# relaymodule.net
KiCad netlist of a schematic drawn in Altium Designer
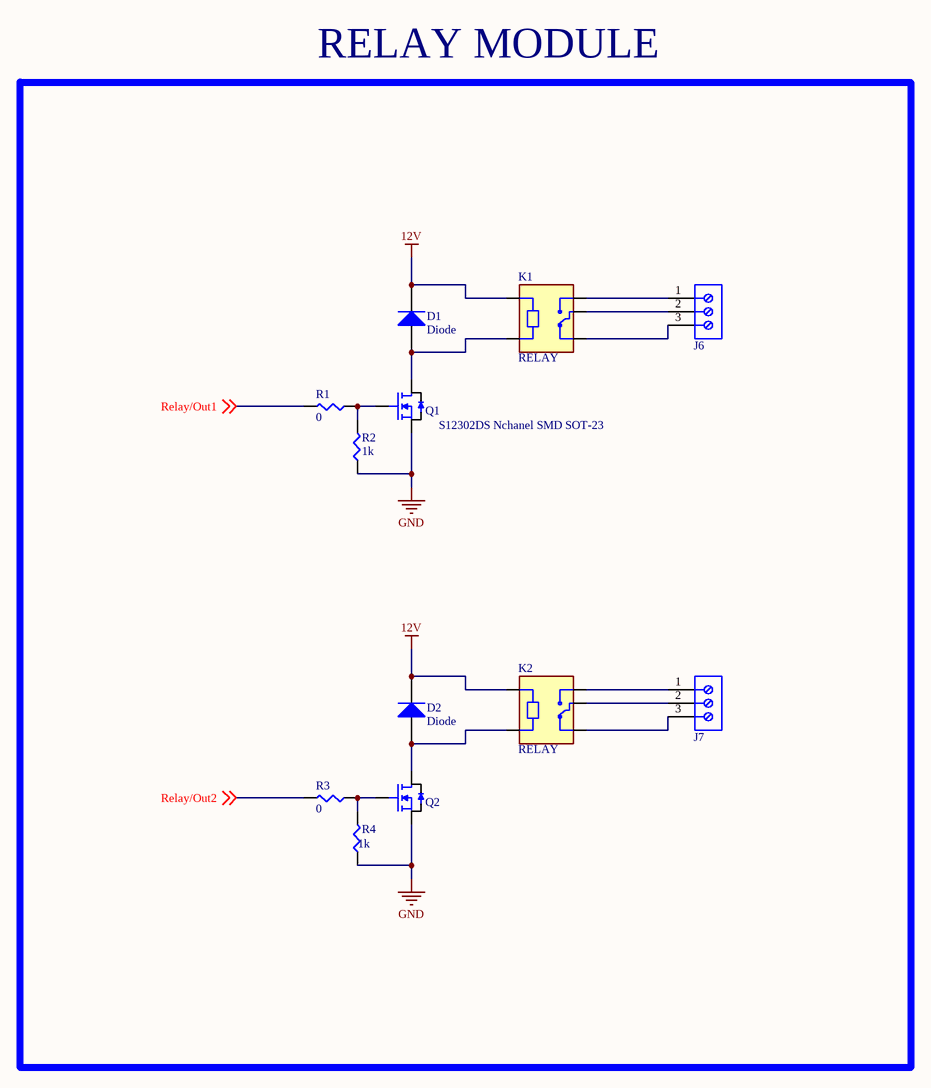
[diagram p0: relaymodule.SchDoc]

(export (version "E")
  (design (tool "Eeschema 10.0.6"))
  (components
    (comp (ref "D1")
      (value "Diode")
      (footprint "SMC")
      (description "Default Diode")
      (fields (field (name "PUBLISHER") "Altium Limited"))
      (libsource (lib "Miscellaneous Devices") (part "Diode"))
    )
    (comp (ref "D2")
      (value "Diode")
      (footprint "SMC")
      (description "Default Diode")
      (fields (field (name "PUBLISHER") "Altium Limited"))
      (libsource (lib "Miscellaneous Devices") (part "Diode"))
    )
    (comp (ref "J6")
      (value "691101710003")
      (footprint "691101710003")
      (description "WR-TBL Series 101 Horizontal Entry Modular, THT, pitch 5mm, 3p")
      (fields (field (name "MANUFACTURER") "Wurth Elektronik"))
      (libsource (lib "PITCH PINS") (part "691101710003"))
    )
    (comp (ref "J7")
      (value "691101710003")
      (footprint "691101710003")
      (description "WR-TBL Series 101 Horizontal Entry Modular, THT, pitch 5mm, 3p")
      (fields (field (name "MANUFACTURER") "Wurth Elektronik"))
      (libsource (lib "PITCH PINS") (part "691101710003"))
    )
    (comp (ref "K1") (value "RELAY") (footprint "RELAY") (libsource (lib "Schlib1") (part "RELAY")))
    (comp (ref "K2") (value "RELAY") (footprint "RELAY") (libsource (lib "Schlib1") (part "RELAY")))
    (comp (ref "Q1")
      (value "S12302DS Nchanel SMD SOT-23")
      (footprint "SOT-23-3N")
      (description "S12302DS Nchanel SMD SOT-23. VDS MAX 20. 400Ma DI")
      (libsource (lib "My mosfet and Transistors Library") (part "S12302DS"))
    )
    (comp (ref "Q2")
      (value "S12302DS Nchanel SMD SOT-23")
      (footprint "SOT-23-3N")
      (description "S12302DS Nchanel SMD SOT-23. VDS MAX 20. 400Ma DI")
      (libsource (lib "My mosfet and Transistors Library") (part "S12302DS"))
    )
    (comp (ref "R1")
      (value "0")
      (footprint "SMD-0805-RES")
      (description "RES SMD 1K OHM 1% 1/8W 0805")
      (fields
        (field (name "PART NUMBER") "ERJ-6ENF1001V")
        (field (name "DIGI-KEY PART NUMBER") "P1.00KCCT-ND")
      )
      (libsource (lib "Panasonic_ERJ_0805") (part "ERJ-6ENF1001V"))
    )
    (comp (ref "R2")
      (value "1k")
      (footprint "SMD-0805-RES")
      (description "RES SMD 1K OHM 1% 1/8W 0805")
      (fields
        (field (name "PART NUMBER") "ERJ-6ENF1001V")
        (field (name "DIGI-KEY PART NUMBER") "P1.00KCCT-ND")
      )
      (libsource (lib "Panasonic_ERJ_0805") (part "ERJ-6ENF1001V"))
    )
    (comp (ref "R3")
      (value "0")
      (footprint "SMD-0805-RES")
      (description "RES SMD 1K OHM 1% 1/8W 0805")
      (fields
        (field (name "PART NUMBER") "ERJ-6ENF1001V")
        (field (name "DIGI-KEY PART NUMBER") "P1.00KCCT-ND")
      )
      (libsource (lib "Panasonic_ERJ_0805") (part "ERJ-6ENF1001V"))
    )
    (comp (ref "R4")
      (value "1k")
      (footprint "SMD-0805-RES")
      (description "RES SMD 1K OHM 1% 1/8W 0805")
      (fields
        (field (name "PART NUMBER") "ERJ-6ENF1001V")
        (field (name "DIGI-KEY PART NUMBER") "P1.00KCCT-ND")
      )
      (libsource (lib "Panasonic_ERJ_0805") (part "ERJ-6ENF1001V"))
    )
  )
  (nets
    (net (code "1") (name "12V") (class "Default")
      (node (ref "D1") (pin "2") (pinfunction "K_2") (pintype "passive"))
      (node (ref "D2") (pin "2") (pinfunction "K_2") (pintype "passive"))
      (node (ref "K1") (pin "A1") (pinfunction "A1_A1") (pintype "passive"))
      (node (ref "K2") (pin "A1") (pinfunction "A1_A1") (pintype "passive"))
    )
    (net (code "2") (name "GND") (class "Default")
      (node (ref "Q1") (pin "2") (pinfunction "Source_2") (pintype "passive"))
      (node (ref "Q2") (pin "2") (pinfunction "Source_2") (pintype "passive"))
      (node (ref "R2") (pin "1") (pinfunction "1_1") (pintype "passive"))
      (node (ref "R4") (pin "1") (pinfunction "1_1") (pintype "passive"))
    )
    (net (code "3") (name "Net-(D1-A)") (class "Default")
      (node (ref "D1") (pin "1") (pinfunction "A_1") (pintype "passive"))
      (node (ref "K1") (pin "A2") (pinfunction "A2_A2") (pintype "passive"))
      (node (ref "Q1") (pin "3") (pinfunction "Drain_3") (pintype "passive"))
    )
    (net (code "4") (name "Net-(D2-A)") (class "Default")
      (node (ref "D2") (pin "1") (pinfunction "A_1") (pintype "passive"))
      (node (ref "K2") (pin "A2") (pinfunction "A2_A2") (pintype "passive"))
      (node (ref "Q2") (pin "3") (pinfunction "Drain_3") (pintype "passive"))
    )
    (net (code "5") (name "Net-(J6-Pad1)") (class "Default")
      (node (ref "J6") (pin "1") (pinfunction "1_1") (pintype "passive"))
      (node (ref "K1") (pin "NO") (pinfunction "NO_NO") (pintype "passive"))
    )
    (net (code "6") (name "Net-(J6-Pad2)") (class "Default")
      (node (ref "J6") (pin "2") (pinfunction "2_2") (pintype "passive"))
      (node (ref "K1") (pin "COM") (pinfunction "COM_COM") (pintype "passive"))
    )
    (net (code "7") (name "Net-(J6-Pad3)") (class "Default")
      (node (ref "J6") (pin "3") (pinfunction "3_3") (pintype "passive"))
      (node (ref "K1") (pin "NC") (pinfunction "NC_NC") (pintype "passive"))
    )
    (net (code "8") (name "Net-(J7-Pad1)") (class "Default")
      (node (ref "J7") (pin "1") (pinfunction "1_1") (pintype "passive"))
      (node (ref "K2") (pin "NO") (pinfunction "NO_NO") (pintype "passive"))
    )
    (net (code "9") (name "Net-(J7-Pad2)") (class "Default")
      (node (ref "J7") (pin "2") (pinfunction "2_2") (pintype "passive"))
      (node (ref "K2") (pin "COM") (pinfunction "COM_COM") (pintype "passive"))
    )
    (net (code "10") (name "Net-(J7-Pad3)") (class "Default")
      (node (ref "J7") (pin "3") (pinfunction "3_3") (pintype "passive"))
      (node (ref "K2") (pin "NC") (pinfunction "NC_NC") (pintype "passive"))
    )
    (net (code "11") (name "Net-(Q1-Gate)") (class "Default")
      (node (ref "Q1") (pin "1") (pinfunction "Gate_1") (pintype "passive"))
      (node (ref "R1") (pin "1") (pinfunction "1_1") (pintype "passive"))
      (node (ref "R2") (pin "2") (pinfunction "2_2") (pintype "passive"))
    )
    (net (code "12") (name "Net-(Q2-Gate)") (class "Default")
      (node (ref "Q2") (pin "1") (pinfunction "Gate_1") (pintype "passive"))
      (node (ref "R3") (pin "1") (pinfunction "1_1") (pintype "passive"))
      (node (ref "R4") (pin "2") (pinfunction "2_2") (pintype "passive"))
    )
    (net (code "13") (name "Relay{slash}Out1") (class "Default")
      (node (ref "R1") (pin "2") (pinfunction "2_2") (pintype "passive"))
    )
    (net (code "14") (name "Relay{slash}Out2") (class "Default")
      (node (ref "R3") (pin "2") (pinfunction "2_2") (pintype "passive"))
    )
  )
)
